# leistung_e7.net
KiCad netlist of a schematic drawn in EAGLE
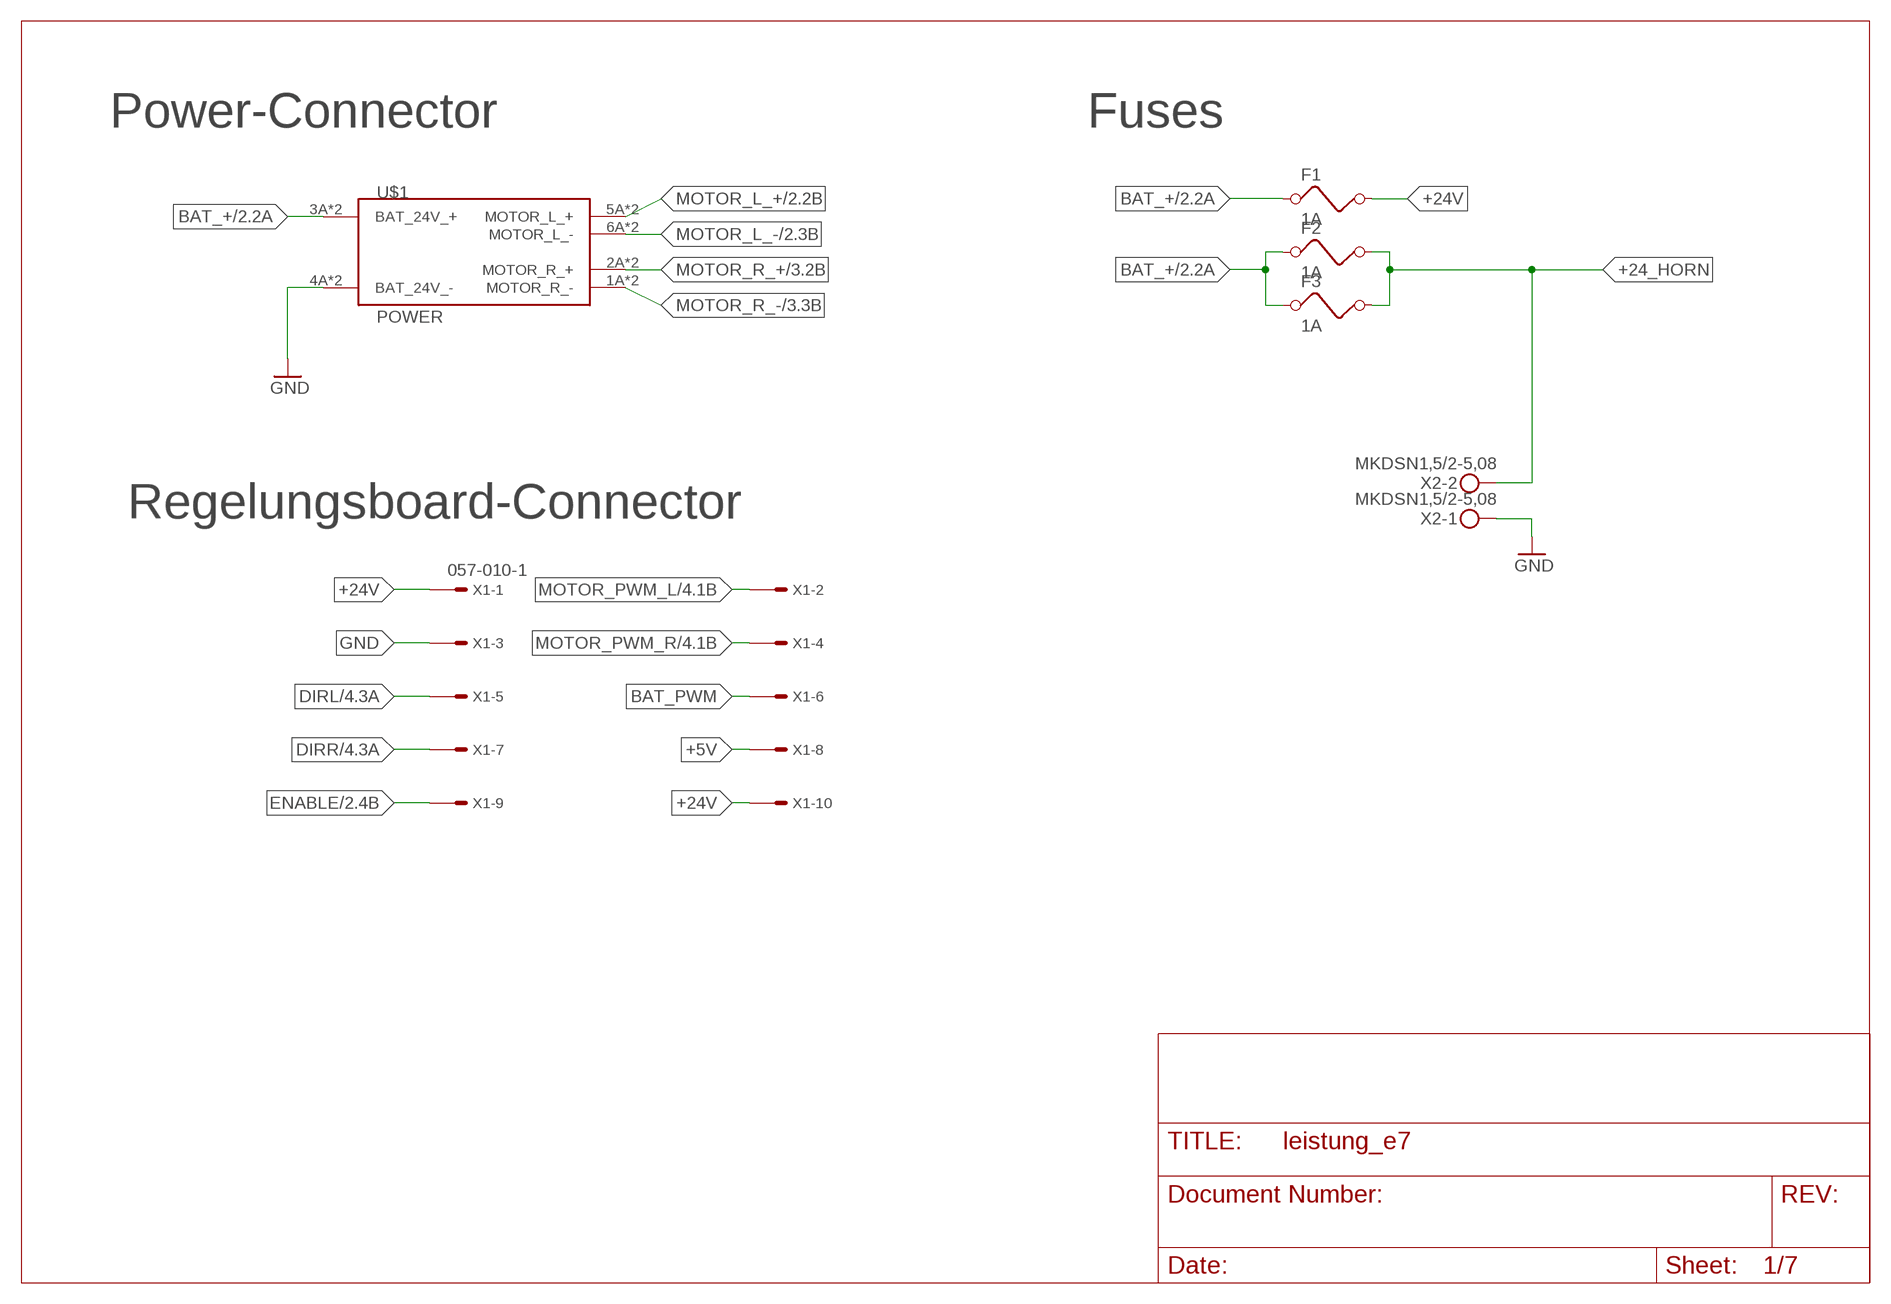
[diagram p0: schematic, sheet 1]
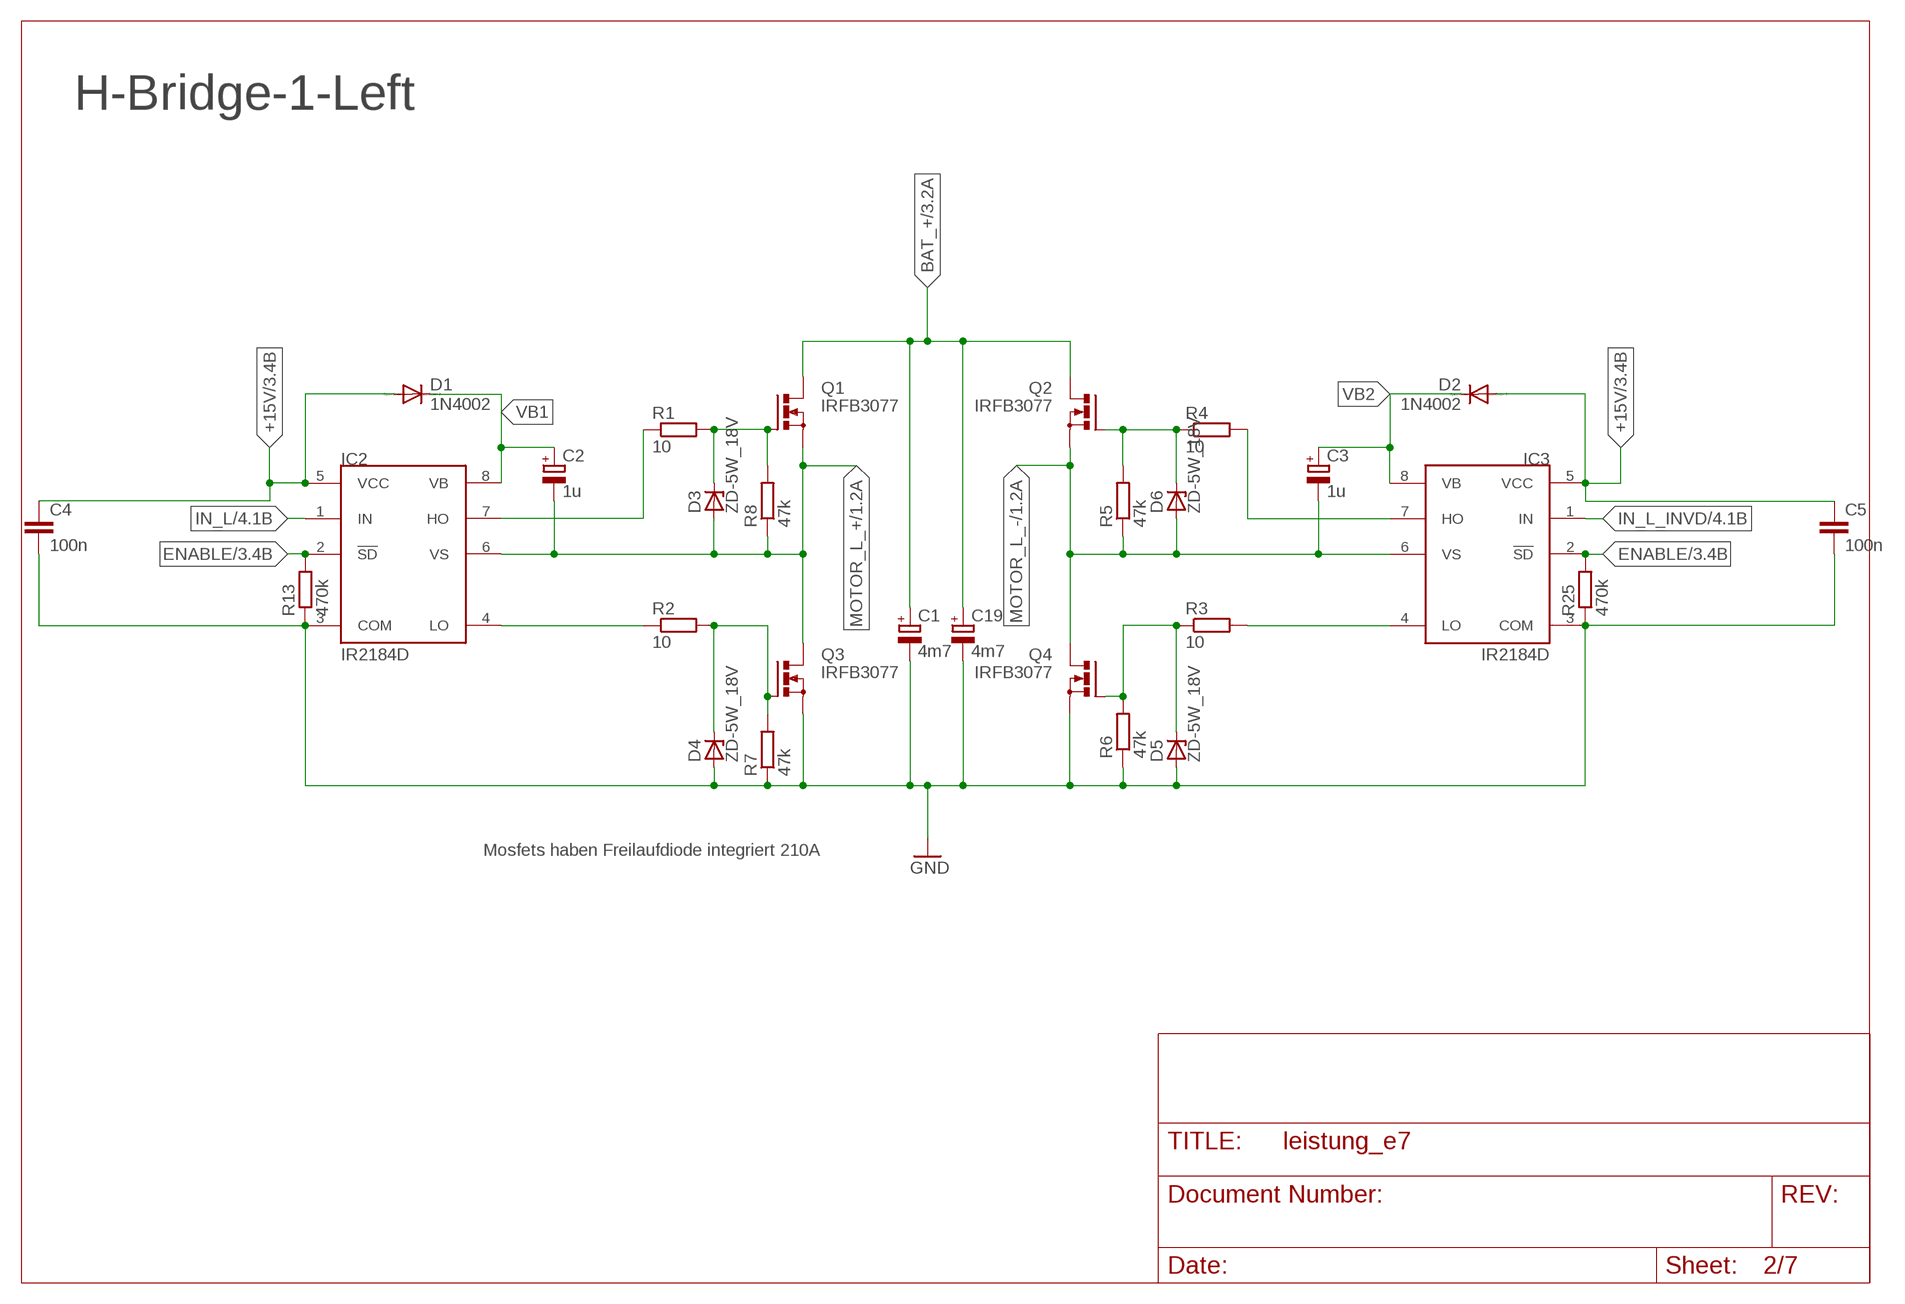
[diagram p1: schematic, sheet 2]
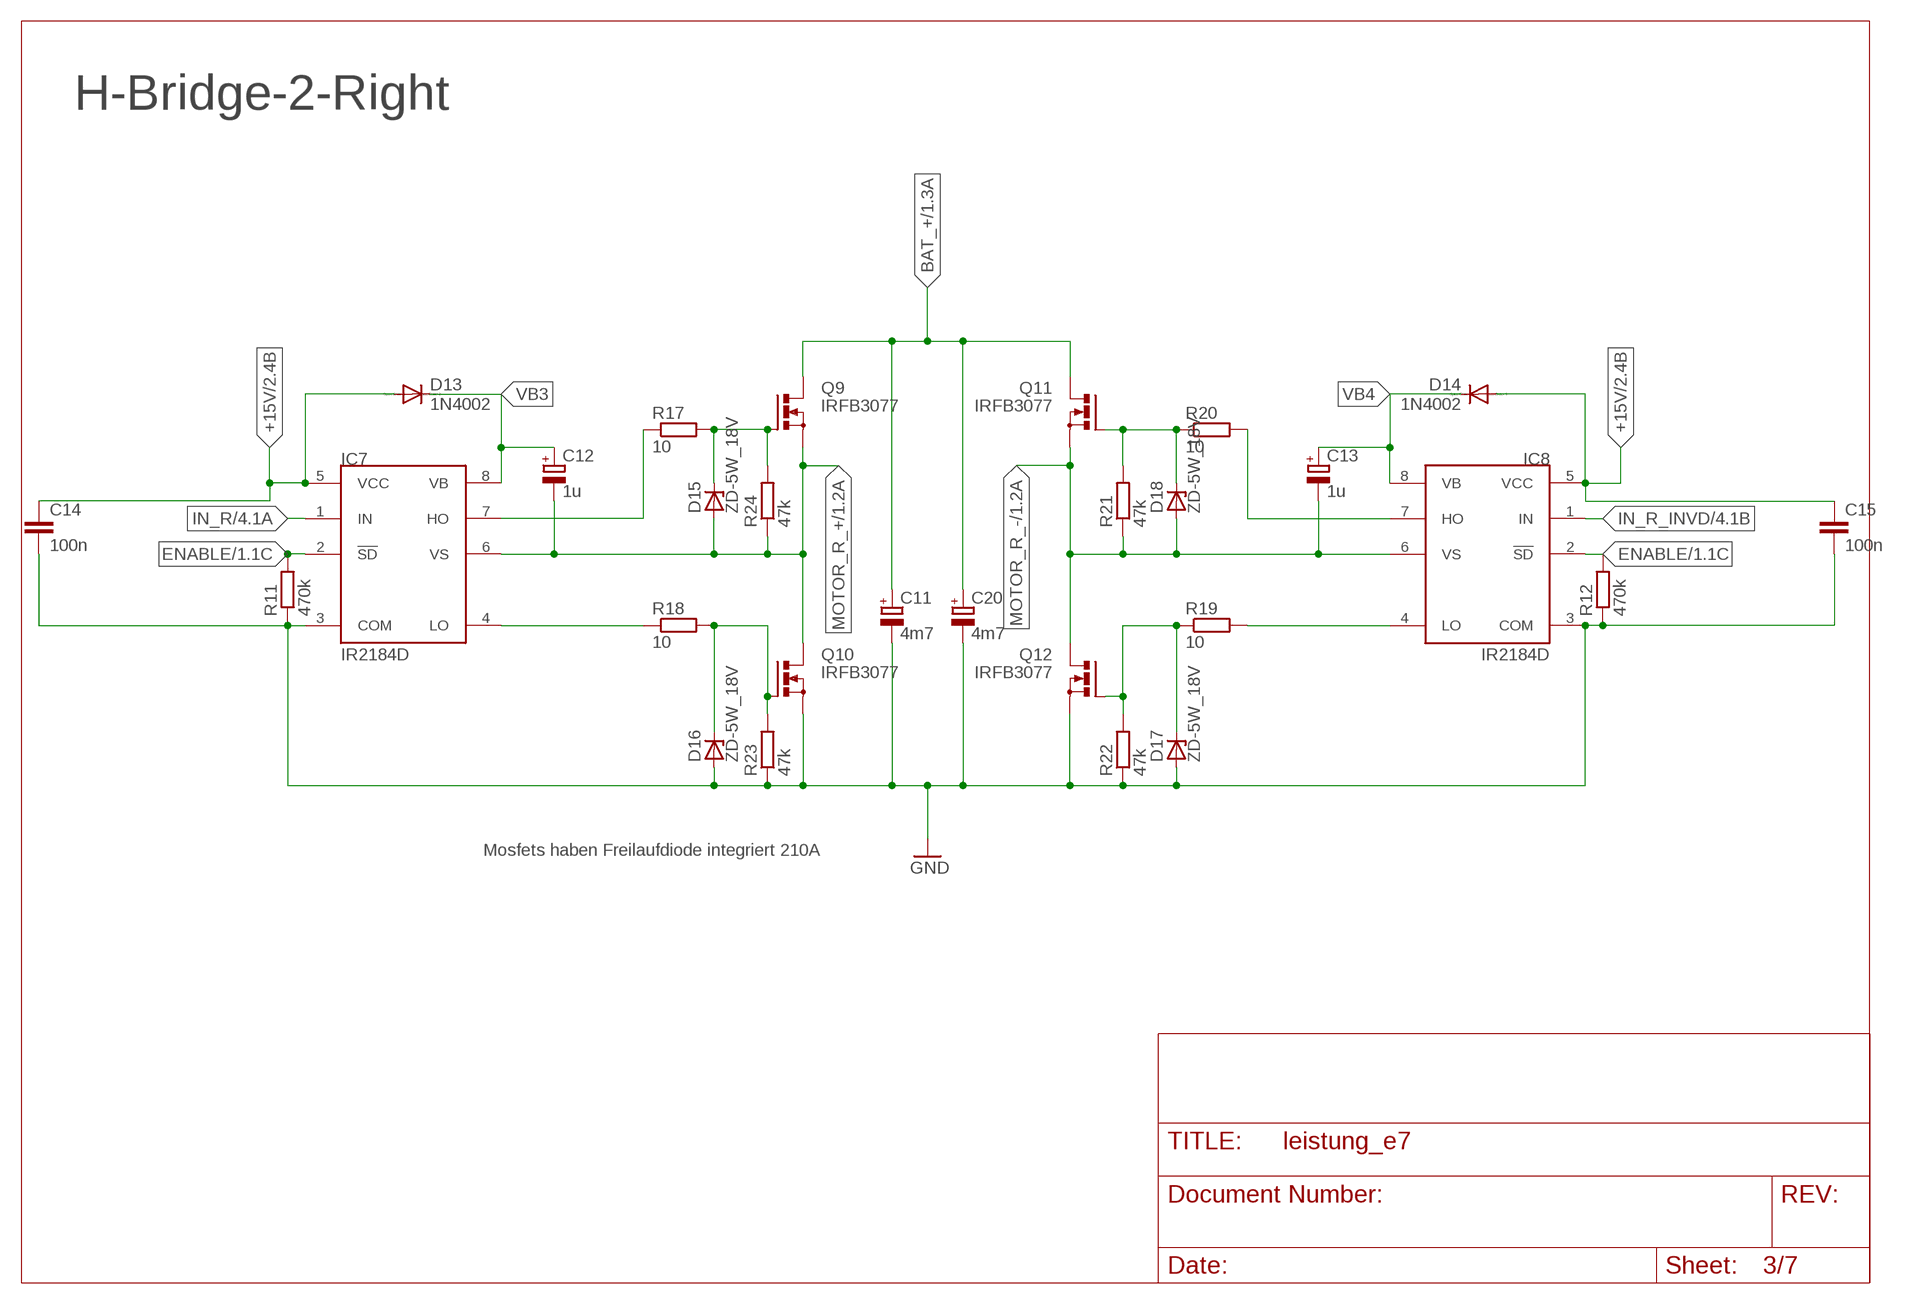
[diagram p2: schematic, sheet 3]
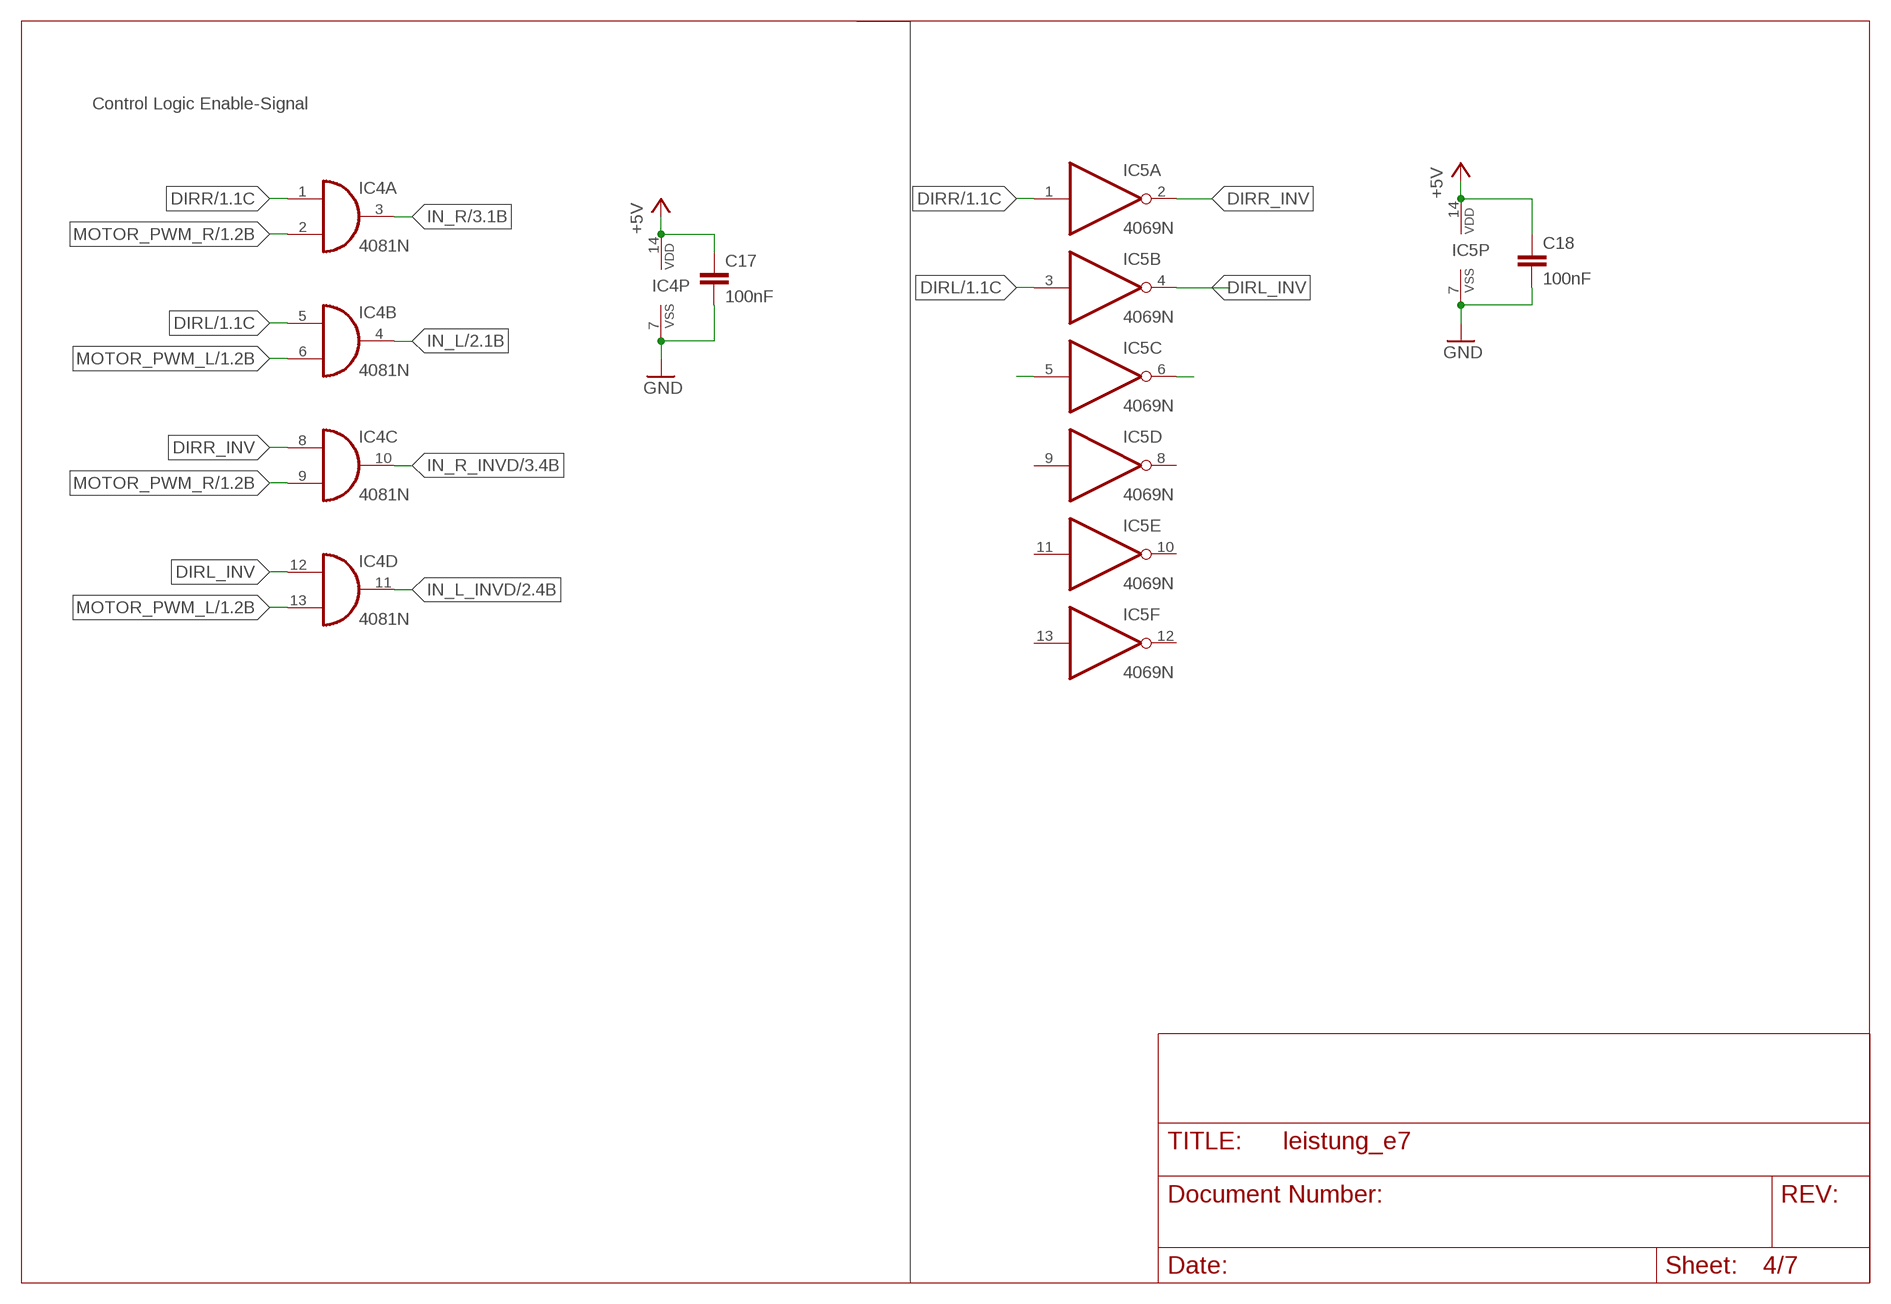
[diagram p3: schematic, sheet 4]
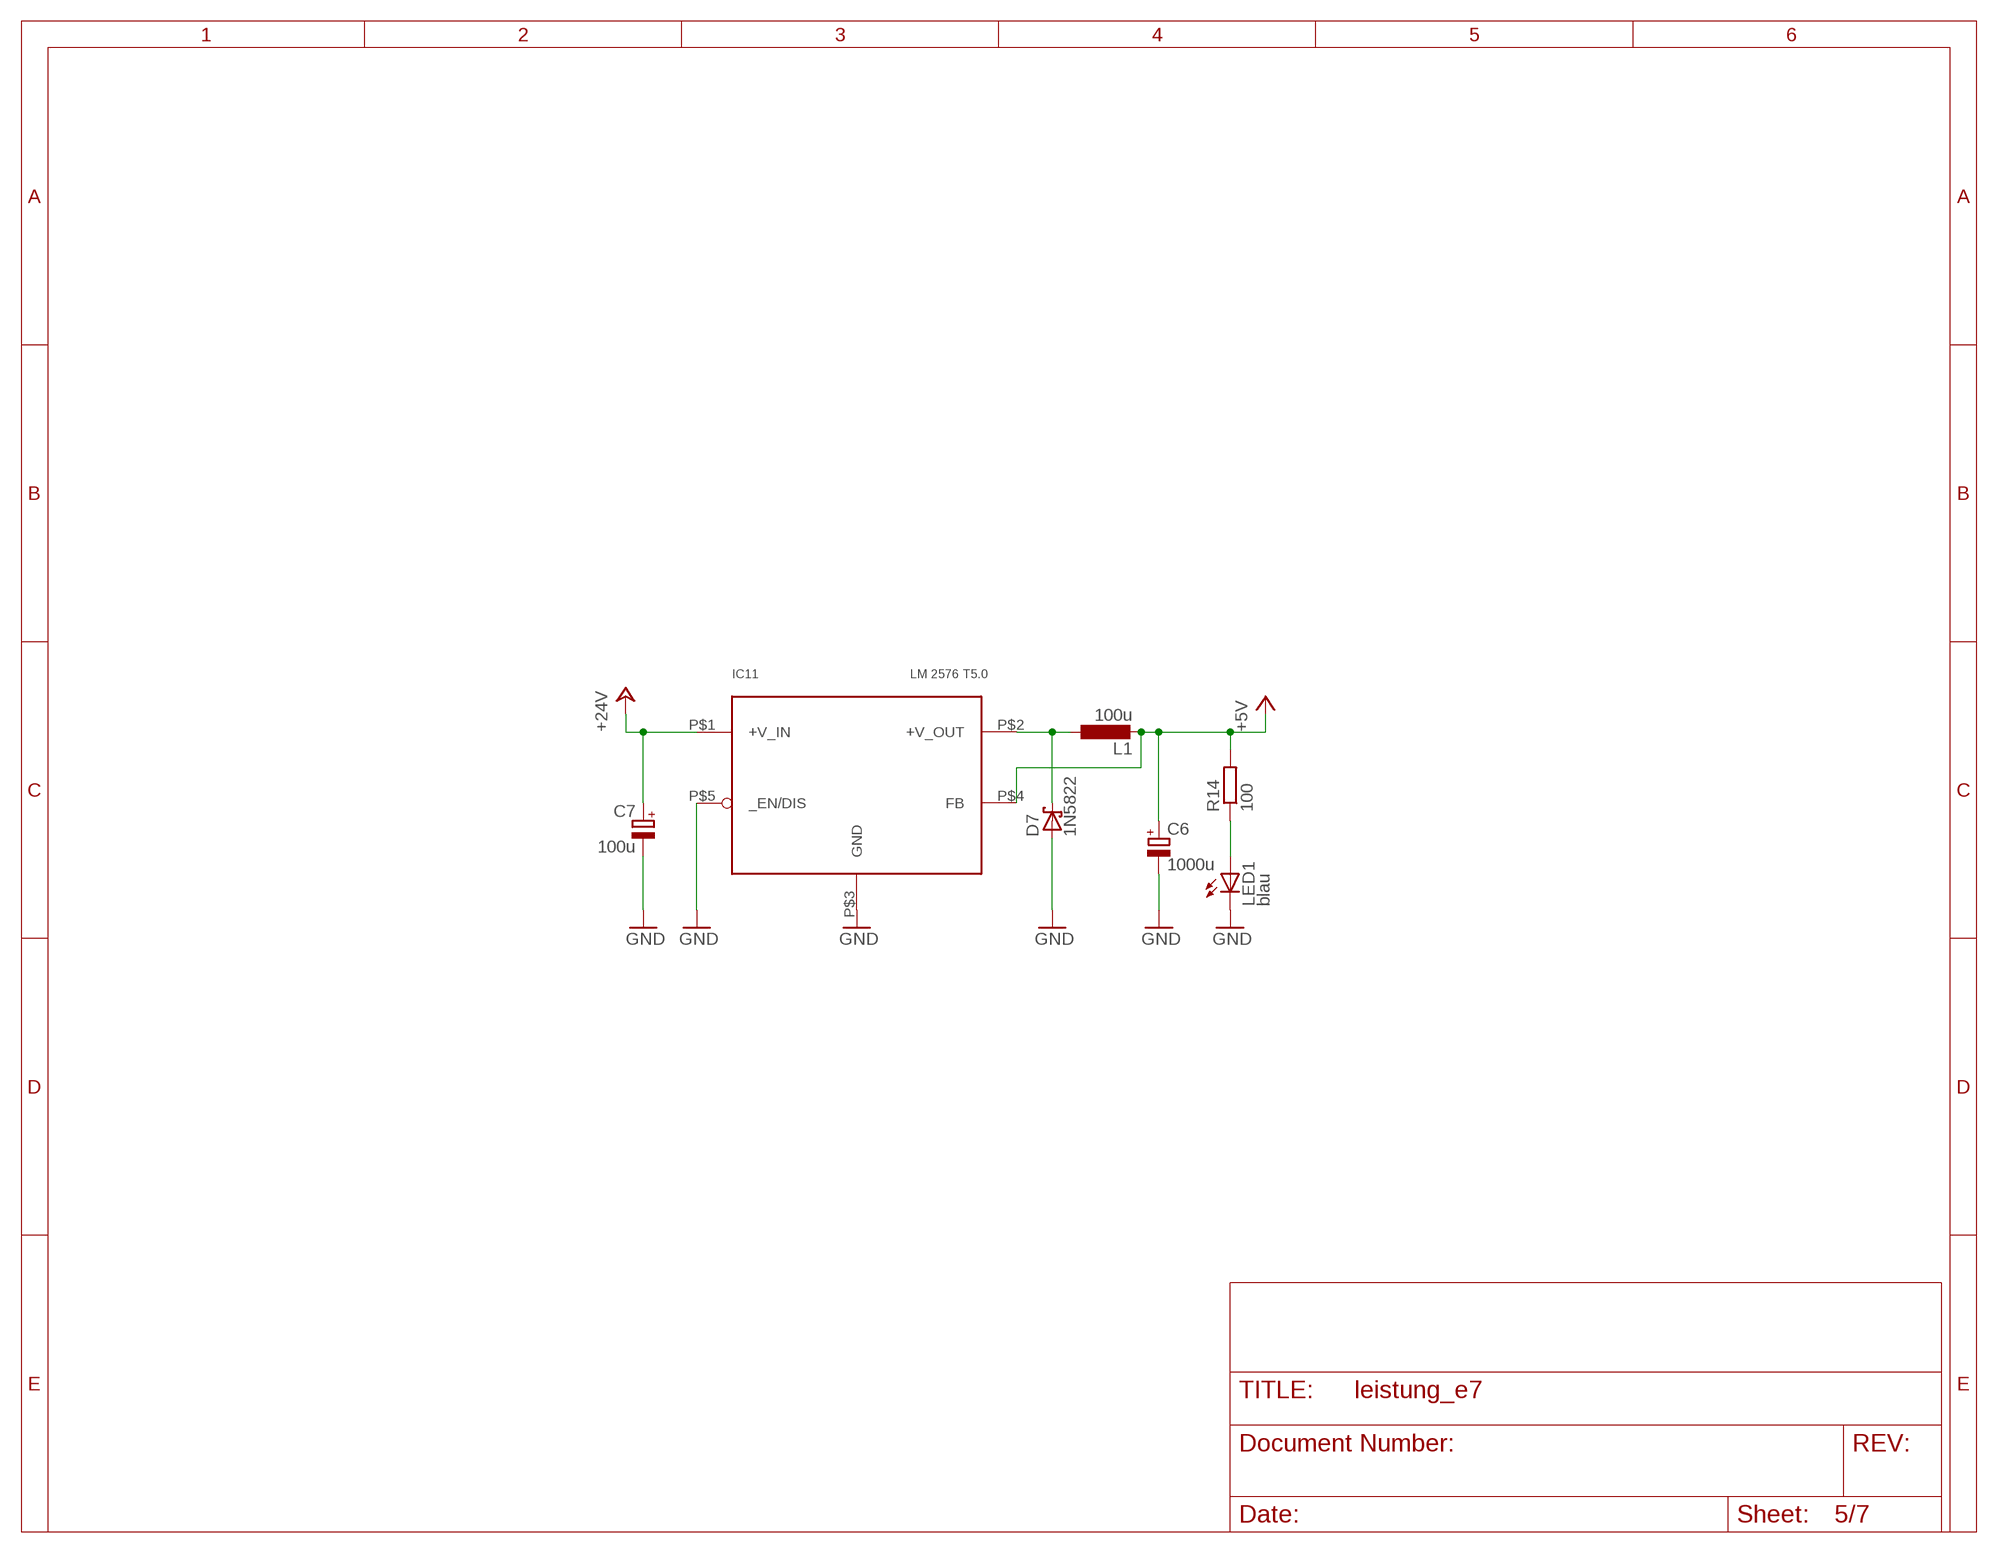
[diagram p4: schematic, sheet 5]
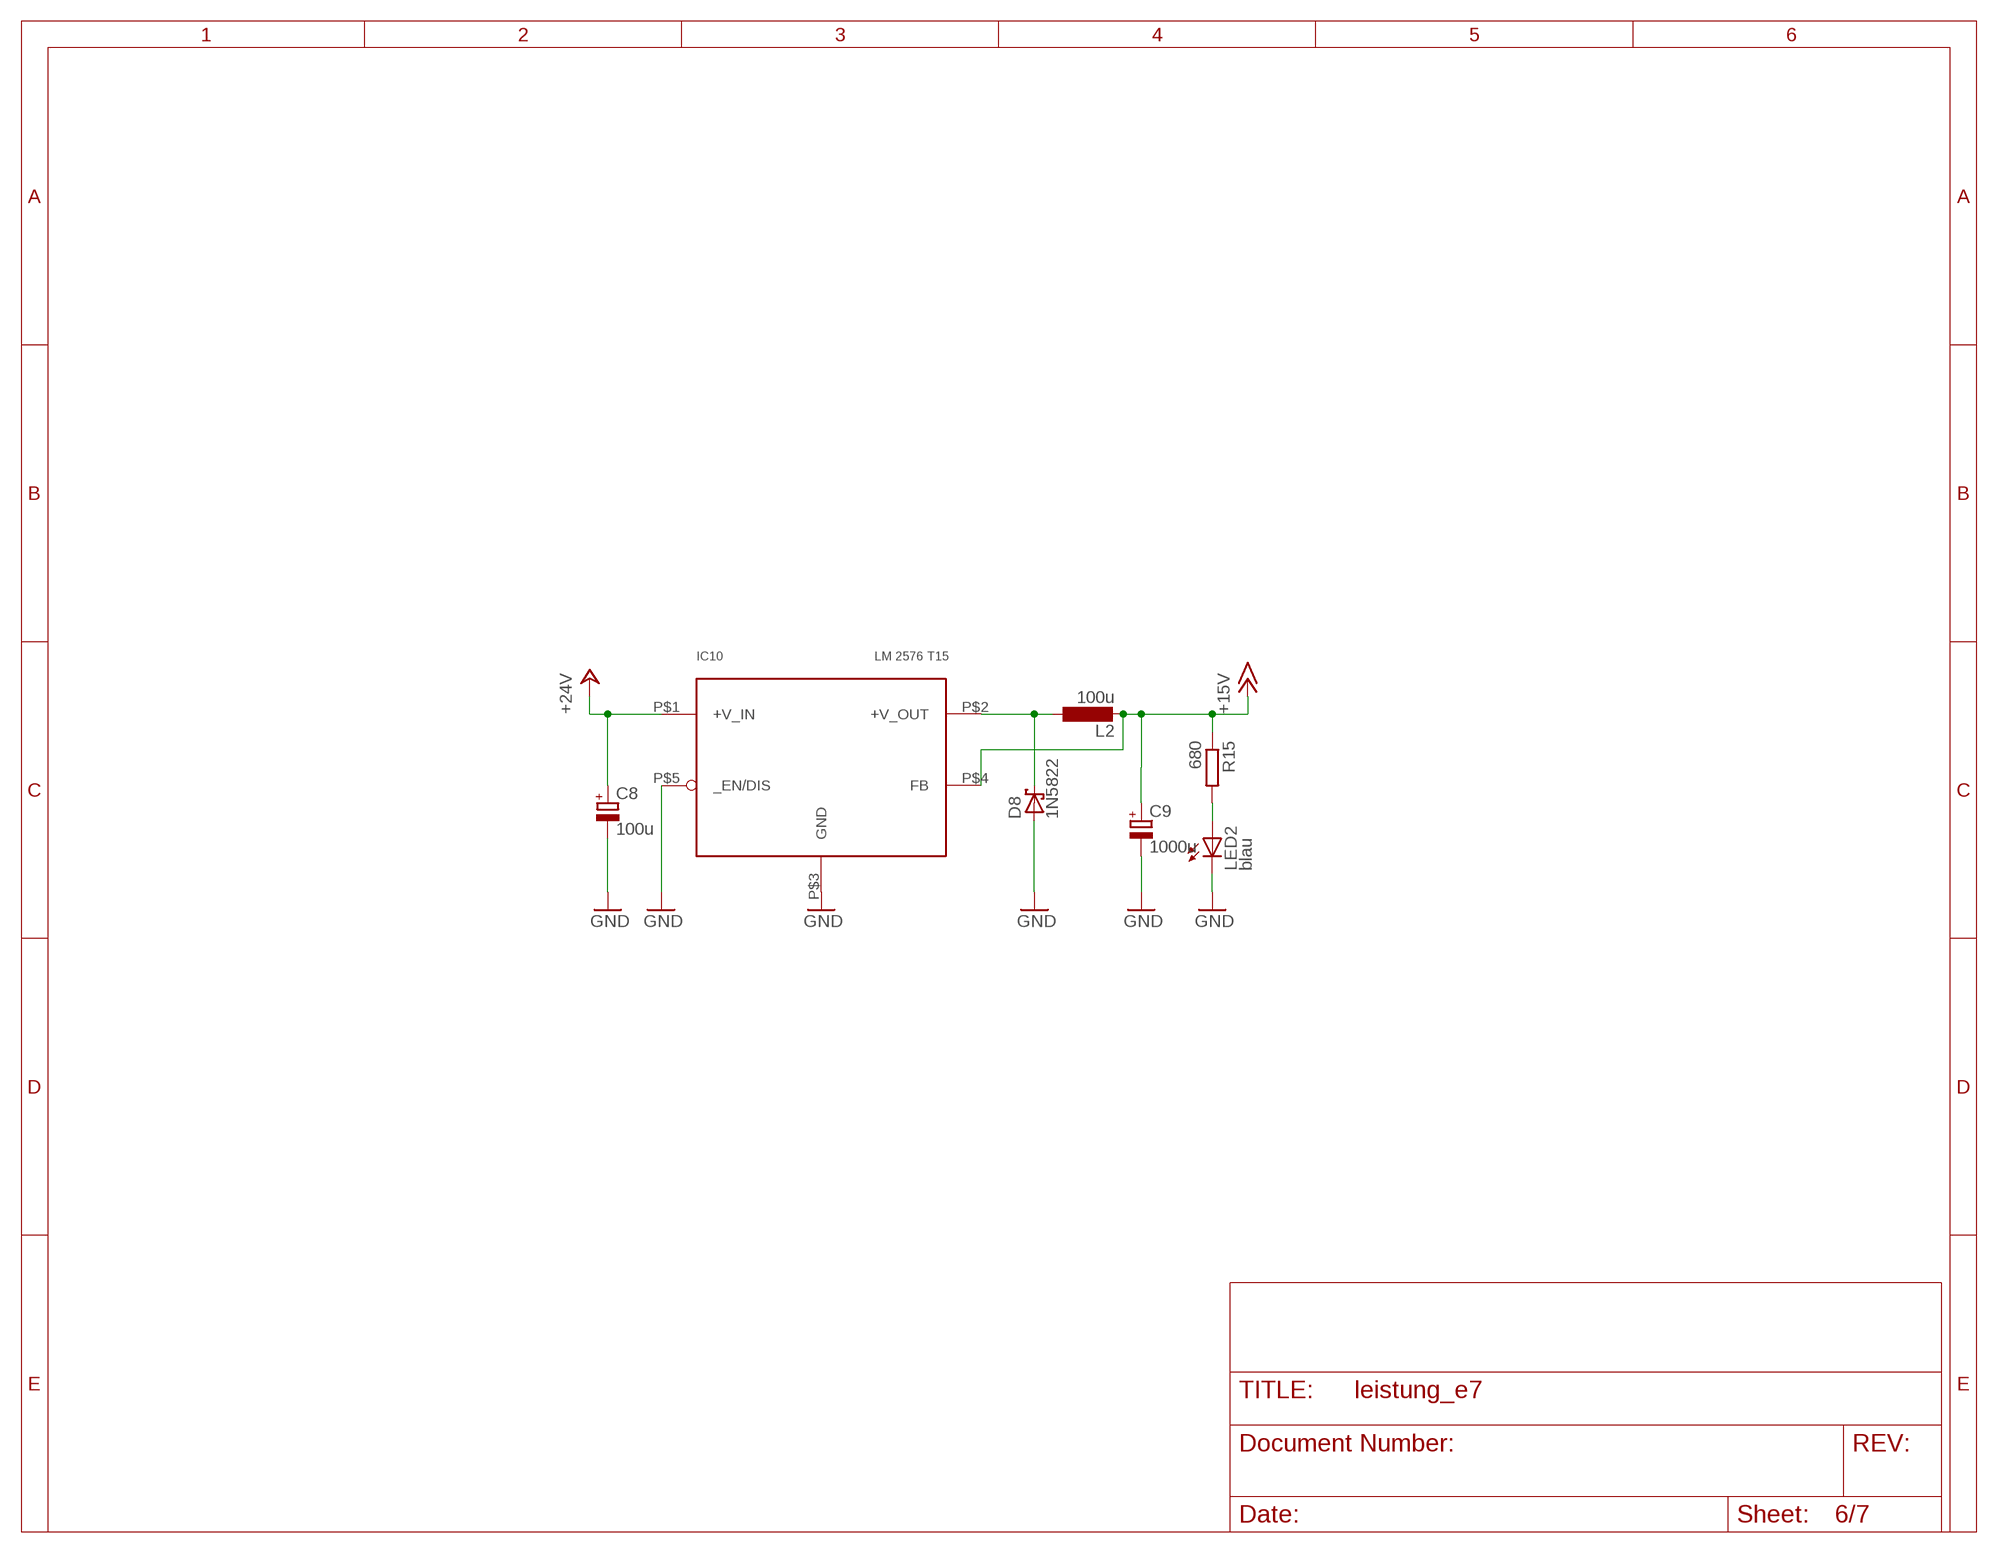
[diagram p5: schematic, sheet 6]
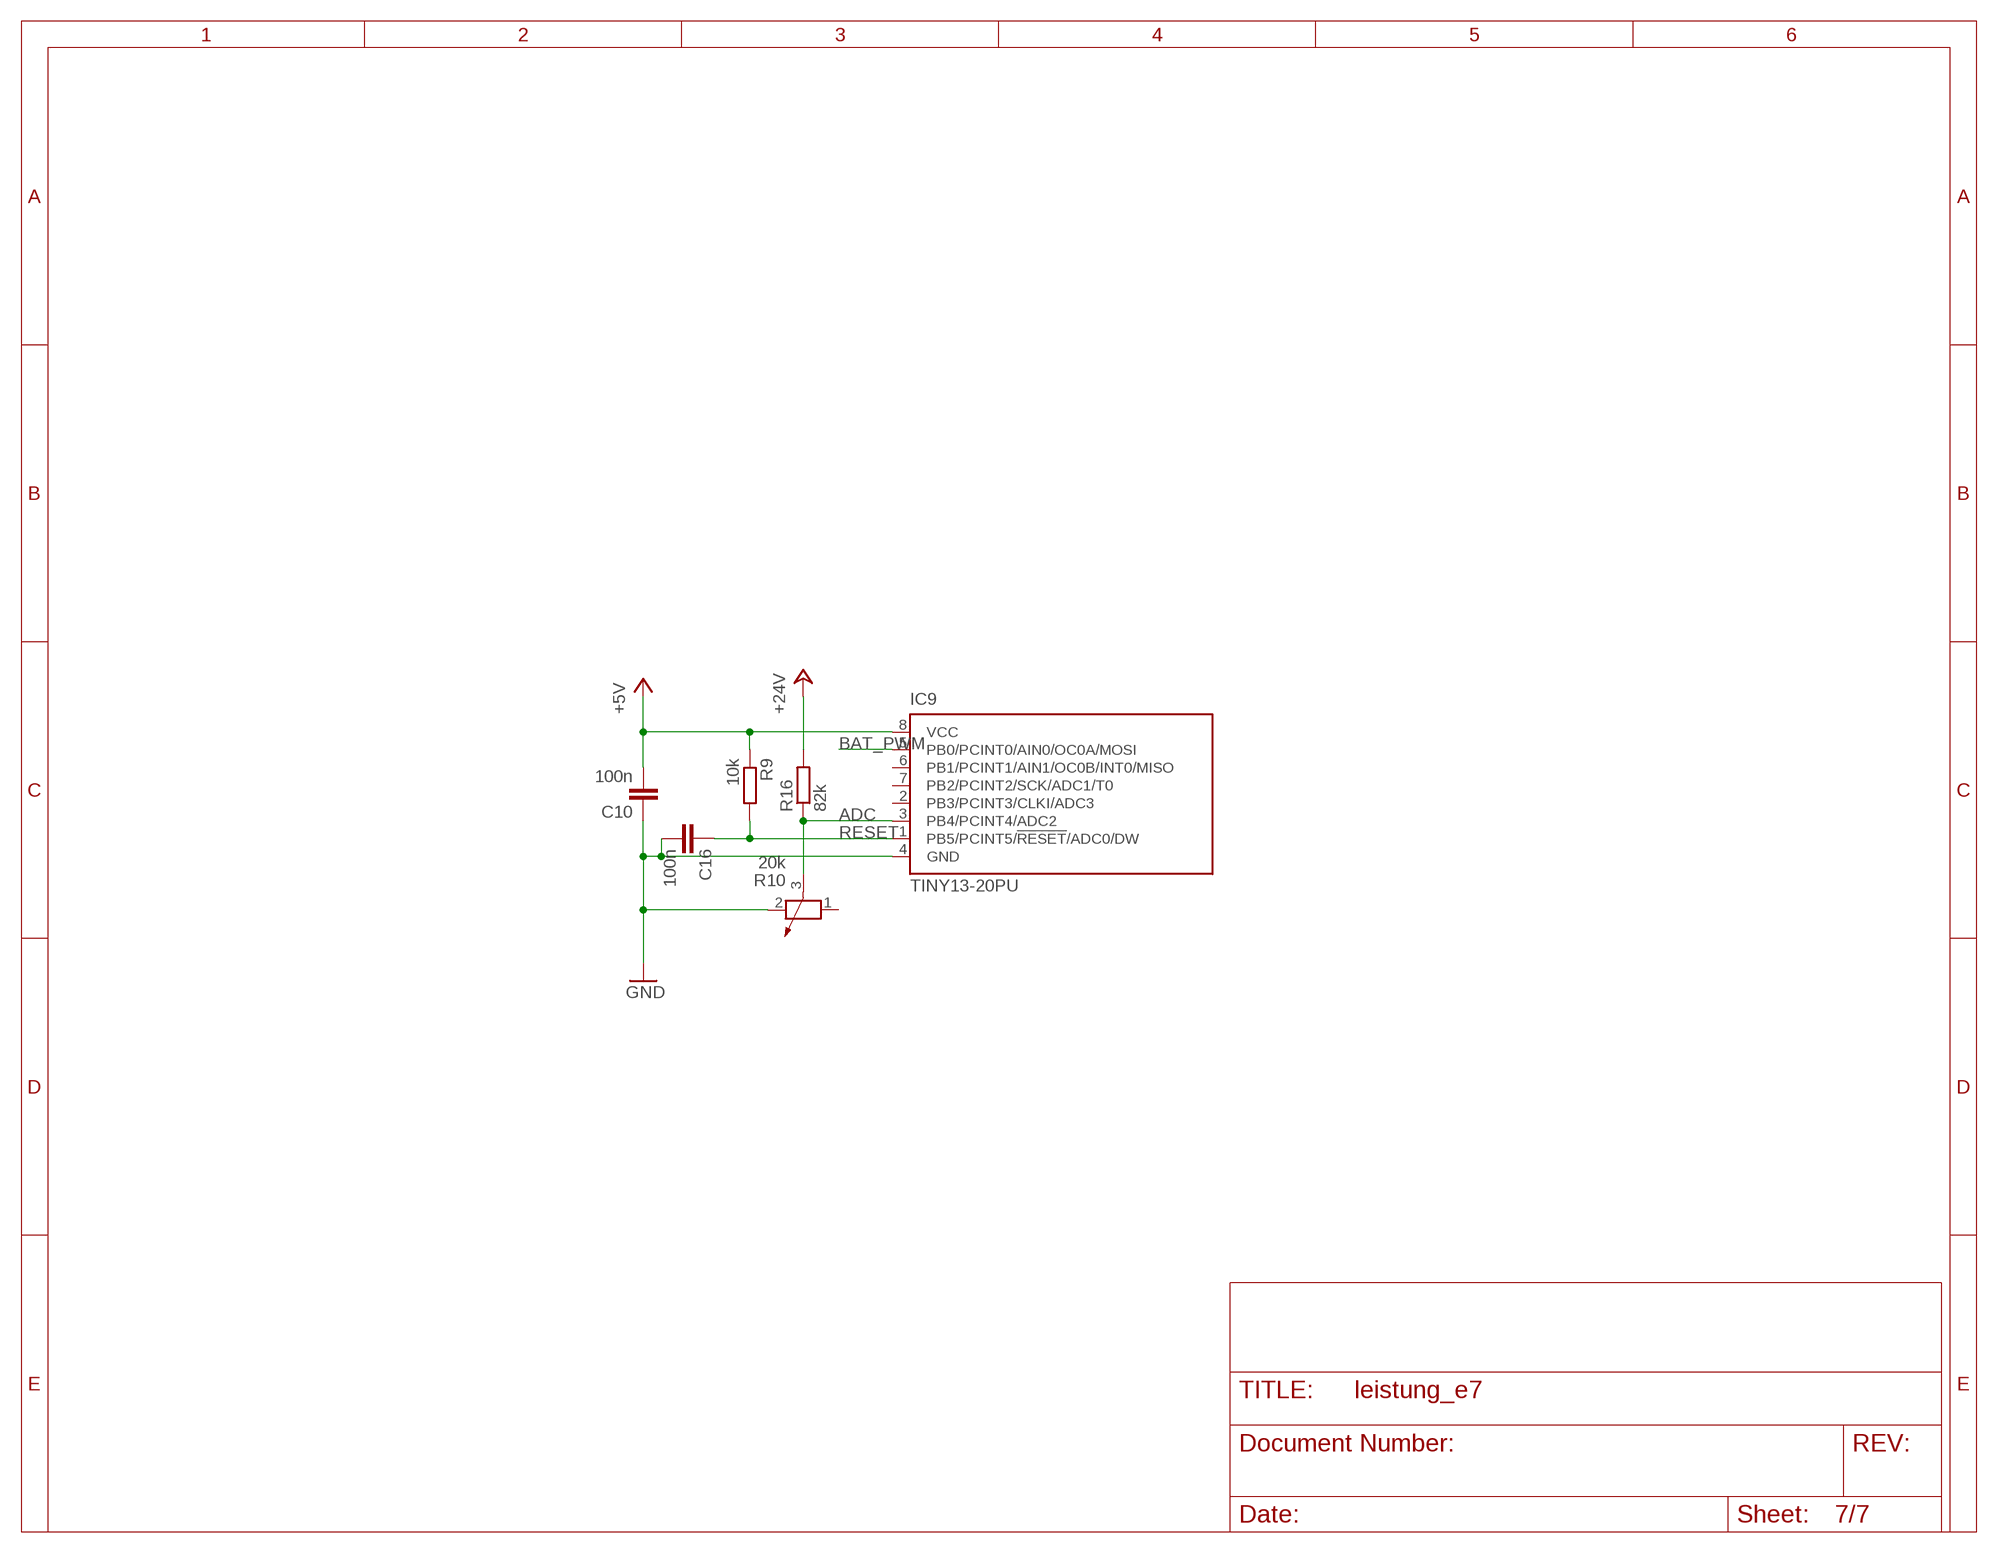
[diagram p6: schematic, sheet 7]

(export (version "E")
  (design (tool "Eeschema 10.0.6"))
  (components
    (comp (ref "C11")
      (value "4m7")
      (footprint "eagle-import:E7,5-18")
      (libsource (lib "eagle-import") (part "CPOL-EUE7.5-18"))
    )
    (comp (ref "C12")
      (value "1u")
      (footprint "eagle-import:E2,5-5")
      (libsource (lib "eagle-import") (part "CPOL-EUE2.5-5"))
    )
    (comp (ref "C13")
      (value "1u")
      (footprint "eagle-import:E2,5-5")
      (libsource (lib "eagle-import") (part "CPOL-EUE2.5-5"))
    )
    (comp (ref "C14")
      (value "100n")
      (footprint "eagle-import:C025-025X050")
      (libsource (lib "eagle-import") (part "C-EU025-025X050"))
    )
    (comp (ref "C15")
      (value "100n")
      (footprint "eagle-import:C025-025X050")
      (libsource (lib "eagle-import") (part "C-EU025-025X050"))
    )
    (comp (ref "C20")
      (value "4m7")
      (footprint "eagle-import:E7,5-18")
      (libsource (lib "eagle-import") (part "CPOL-EUE7.5-18"))
    )
    (comp (ref "D13")
      (value "1N4002")
      (footprint "eagle-import:DO41-10")
      (libsource (lib "eagle-import") (part "1N4004"))
    )
    (comp (ref "D14")
      (value "1N4002")
      (footprint "eagle-import:DO41-10")
      (libsource (lib "eagle-import") (part "1N4004"))
    )
    (comp (ref "D15")
      (value "ZD-5W_18V")
      (footprint "eagle-import:ZDIO-10")
      (libsource (lib "eagle-import") (part "ZENER-DIODEZD-10"))
    )
    (comp (ref "D16")
      (value "ZD-5W_18V")
      (footprint "eagle-import:ZDIO-10")
      (libsource (lib "eagle-import") (part "ZENER-DIODEZD-10"))
    )
    (comp (ref "D17")
      (value "ZD-5W_18V")
      (footprint "eagle-import:ZDIO-10")
      (libsource (lib "eagle-import") (part "ZENER-DIODEZD-10"))
    )
    (comp (ref "D18")
      (value "ZD-5W_18V")
      (footprint "eagle-import:ZDIO-10")
      (libsource (lib "eagle-import") (part "ZENER-DIODEZD-10"))
    )
    (comp (ref "IC7")
      (value "IR2184D")
      (footprint "eagle-import:DIL08")
      (libsource (lib "eagle-import") (part "IR2184D"))
    )
    (comp (ref "IC8")
      (value "IR2184D")
      (footprint "eagle-import:DIL08")
      (libsource (lib "eagle-import") (part "IR2184D"))
    )
    (comp (ref "Q9")
      (value "IRFB3077")
      (footprint "eagle-import:TO220BV")
      (libsource (lib "eagle-import") (part "PMOSFET_NTO220BV"))
    )
    (comp (ref "Q10")
      (value "IRFB3077")
      (footprint "eagle-import:TO220BV")
      (libsource (lib "eagle-import") (part "PMOSFET_NTO220BV"))
    )
    (comp (ref "Q11")
      (value "IRFB3077")
      (footprint "eagle-import:TO220BV")
      (libsource (lib "eagle-import") (part "PMOSFET_NTO220BV"))
    )
    (comp (ref "Q12")
      (value "IRFB3077")
      (footprint "eagle-import:TO220BV")
      (libsource (lib "eagle-import") (part "PMOSFET_NTO220BV"))
    )
    (comp (ref "R11")
      (value "470k")
      (footprint "eagle-import:0207_7")
      (libsource (lib "eagle-import") (part "R-EU_0207/7"))
    )
    (comp (ref "R12")
      (value "470k")
      (footprint "eagle-import:0207_7")
      (libsource (lib "eagle-import") (part "R-EU_0207/7"))
    )
    (comp (ref "R17")
      (value "10")
      (footprint "eagle-import:0207_7")
      (libsource (lib "eagle-import") (part "R-EU_0207/7"))
    )
    (comp (ref "R18")
      (value "10")
      (footprint "eagle-import:0207_7")
      (libsource (lib "eagle-import") (part "R-EU_0207/7"))
    )
    (comp (ref "R19")
      (value "10")
      (footprint "eagle-import:0207_7")
      (libsource (lib "eagle-import") (part "R-EU_0207/7"))
    )
    (comp (ref "R20")
      (value "10")
      (footprint "eagle-import:0207_7")
      (libsource (lib "eagle-import") (part "R-EU_0207/7"))
    )
    (comp (ref "R21")
      (value "47k")
      (footprint "eagle-import:0207_7")
      (libsource (lib "eagle-import") (part "R-EU_0207/7"))
    )
    (comp (ref "R22")
      (value "47k")
      (footprint "eagle-import:0207_7")
      (libsource (lib "eagle-import") (part "R-EU_0207/7"))
    )
    (comp (ref "R23")
      (value "47k")
      (footprint "eagle-import:0207_7")
      (libsource (lib "eagle-import") (part "R-EU_0207/7"))
    )
    (comp (ref "R24")
      (value "47k")
      (footprint "eagle-import:0207_7")
      (libsource (lib "eagle-import") (part "R-EU_0207/7"))
    )
    (comp (ref "C6")
      (value "1000u")
      (footprint "eagle-import:E5-13")
      (libsource (lib "eagle-import") (part "CPOL-EUE5-13"))
    )
    (comp (ref "C7")
      (value "100u")
      (footprint "eagle-import:E2,5-4R")
      (libsource (lib "eagle-import") (part "rcl@1_CPOL-EUE2.5-5V"))
    )
    (comp (ref "D7")
      (value "1N5822")
      (footprint "eagle-import:CB417-15")
      (libsource (lib "eagle-import") (part "SCHOTTKY-DIODECB417-15"))
    )
    (comp (ref "IC11")
      (value "LM 2576 T5.0")
      (footprint "eagle-import:TO220-5_STAGGERED")
      (libsource (lib "eagle-import") (part "LM2576-T05D"))
    )
    (comp (ref "L1")
      (value "100u")
      (footprint "eagle-import:0207_10")
      (libsource (lib "eagle-import") (part "L-EU0207/10"))
    )
    (comp (ref "LED1")
      (value "blau")
      (footprint "eagle-import:LED3MM")
      (libsource (lib "eagle-import") (part "LED3MM"))
    )
    (comp (ref "R14")
      (value "100")
      (footprint "eagle-import:0207_10")
      (libsource (lib "eagle-import") (part "rcl@1_R-EU_0207/10"))
    )
    (comp (ref "C10")
      (value "100n")
      (footprint "eagle-import:C025-025X050")
      (libsource (lib "eagle-import") (part "rcl@1_C-EU025-025X050"))
    )
    (comp (ref "C16")
      (value "100n")
      (footprint "eagle-import:C025-025X050")
      (libsource (lib "eagle-import") (part "rcl@1_C-EU025-025X050"))
    )
    (comp (ref "IC9")
      (value "TINY13-20PU")
      (footprint "eagle-import:DIL08")
      (fields (field (name "MPN") "ATTINY13-20PU"))
      (libsource (lib "eagle-import") (part "TINY13PU-20"))
    )
    (comp (ref "R9")
      (value "10k")
      (footprint "eagle-import:0207_10")
      (libsource (lib "eagle-import") (part "rcl@1_R-EU_0207/10"))
    )
    (comp (ref "R10")
      (value "20k")
      (footprint "eagle-import:PT-10")
      (libsource (lib "eagle-import") (part "POTENTIOMETER_PT-10"))
    )
    (comp (ref "R16")
      (value "82k")
      (footprint "eagle-import:0207_10")
      (libsource (lib "eagle-import") (part "rcl@1_R-EU_0207/10"))
    )
    (comp (ref "F1")
      (value "1A")
      (footprint "eagle-import:FUSE")
      (libsource (lib "eagle-import") (part "FUSE"))
    )
    (comp (ref "F2")
      (value "1A")
      (footprint "eagle-import:FUSE")
      (libsource (lib "eagle-import") (part "FUSE"))
    )
    (comp (ref "F3")
      (value "1A")
      (footprint "eagle-import:FUSE")
      (libsource (lib "eagle-import") (part "FUSE"))
    )
    (comp (ref "U$1")
      (value "POWER")
      (footprint "eagle-import:CON_POWER")
      (libsource (lib "eagle-import") (part "POWER"))
    )
    (comp (ref "X1")
      (value "057-010-1")
      (footprint "eagle-import:057-010-1")
      (libsource (lib "eagle-import") (part "057-010-1"))
    )
    (comp (ref "X2")
      (value "MKDSN1,5/2-5,08")
      (footprint "eagle-import:MKDSN1,5_2-5,08")
      (libsource (lib "eagle-import") (part "MKDSN1,5/2-5,08"))
    )
    (comp (ref "C17")
      (value "100nF")
      (footprint "eagle-import:C025-025X050")
      (libsource (lib "eagle-import") (part "C-EU025-025X050"))
    )
    (comp (ref "C18")
      (value "100nF")
      (footprint "eagle-import:C025-025X050")
      (libsource (lib "eagle-import") (part "C-EU025-025X050"))
    )
    (comp (ref "IC4")
      (value "4081N")
      (footprint "eagle-import:DIL14")
      (libsource (lib "eagle-import") (part "4081N"))
    )
    (comp (ref "IC5")
      (value "4069N")
      (footprint "eagle-import:DIL14")
      (libsource (lib "eagle-import") (part "4069N"))
    )
    (comp (ref "C1")
      (value "4m7")
      (footprint "eagle-import:E7,5-18")
      (libsource (lib "eagle-import") (part "CPOL-EUE7.5-18"))
    )
    (comp (ref "C2")
      (value "1u")
      (footprint "eagle-import:E2,5-5")
      (libsource (lib "eagle-import") (part "CPOL-EUE2.5-5"))
    )
    (comp (ref "C3")
      (value "1u")
      (footprint "eagle-import:E2,5-5")
      (libsource (lib "eagle-import") (part "CPOL-EUE2.5-5"))
    )
    (comp (ref "C4")
      (value "100n")
      (footprint "eagle-import:C025-025X050")
      (libsource (lib "eagle-import") (part "C-EU025-025X050"))
    )
    (comp (ref "C5")
      (value "100n")
      (footprint "eagle-import:C025-025X050")
      (libsource (lib "eagle-import") (part "C-EU025-025X050"))
    )
    (comp (ref "C19")
      (value "4m7")
      (footprint "eagle-import:E7,5-18")
      (libsource (lib "eagle-import") (part "CPOL-EUE7.5-18"))
    )
    (comp (ref "D1")
      (value "1N4002")
      (footprint "eagle-import:DO41-10")
      (libsource (lib "eagle-import") (part "1N4004"))
    )
    (comp (ref "D2")
      (value "1N4002")
      (footprint "eagle-import:DO41-10")
      (libsource (lib "eagle-import") (part "1N4004"))
    )
    (comp (ref "D3")
      (value "ZD-5W_18V")
      (footprint "eagle-import:ZDIO-10")
      (libsource (lib "eagle-import") (part "ZENER-DIODEZD-10"))
    )
    (comp (ref "D4")
      (value "ZD-5W_18V")
      (footprint "eagle-import:ZDIO-10")
      (libsource (lib "eagle-import") (part "ZENER-DIODEZD-10"))
    )
    (comp (ref "D5")
      (value "ZD-5W_18V")
      (footprint "eagle-import:ZDIO-10")
      (libsource (lib "eagle-import") (part "ZENER-DIODEZD-10"))
    )
    (comp (ref "D6")
      (value "ZD-5W_18V")
      (footprint "eagle-import:ZDIO-10")
      (libsource (lib "eagle-import") (part "ZENER-DIODEZD-10"))
    )
    (comp (ref "IC2")
      (value "IR2184D")
      (footprint "eagle-import:DIL08")
      (libsource (lib "eagle-import") (part "IR2184D"))
    )
    (comp (ref "IC3")
      (value "IR2184D")
      (footprint "eagle-import:DIL08")
      (libsource (lib "eagle-import") (part "IR2184D"))
    )
    (comp (ref "Q1")
      (value "IRFB3077")
      (footprint "eagle-import:TO220BV")
      (libsource (lib "eagle-import") (part "PMOSFET_NTO220BV"))
    )
    (comp (ref "Q2")
      (value "IRFB3077")
      (footprint "eagle-import:TO220BV")
      (libsource (lib "eagle-import") (part "PMOSFET_NTO220BV"))
    )
    (comp (ref "Q3")
      (value "IRFB3077")
      (footprint "eagle-import:TO220BV")
      (libsource (lib "eagle-import") (part "PMOSFET_NTO220BV"))
    )
    (comp (ref "Q4")
      (value "IRFB3077")
      (footprint "eagle-import:TO220BV")
      (libsource (lib "eagle-import") (part "PMOSFET_NTO220BV"))
    )
    (comp (ref "R1")
      (value "10")
      (footprint "eagle-import:0207_7")
      (libsource (lib "eagle-import") (part "R-EU_0207/7"))
    )
    (comp (ref "R2")
      (value "10")
      (footprint "eagle-import:0207_7")
      (libsource (lib "eagle-import") (part "R-EU_0207/7"))
    )
    (comp (ref "R3")
      (value "10")
      (footprint "eagle-import:0207_7")
      (libsource (lib "eagle-import") (part "R-EU_0207/7"))
    )
    (comp (ref "R4")
      (value "10")
      (footprint "eagle-import:0207_7")
      (libsource (lib "eagle-import") (part "R-EU_0207/7"))
    )
    (comp (ref "R5")
      (value "47k")
      (footprint "eagle-import:0207_7")
      (libsource (lib "eagle-import") (part "R-EU_0207/7"))
    )
    (comp (ref "R6")
      (value "47k")
      (footprint "eagle-import:0207_7")
      (libsource (lib "eagle-import") (part "R-EU_0207/7"))
    )
    (comp (ref "R7")
      (value "47k")
      (footprint "eagle-import:0207_7")
      (libsource (lib "eagle-import") (part "R-EU_0207/7"))
    )
    (comp (ref "R8")
      (value "47k")
      (footprint "eagle-import:0207_7")
      (libsource (lib "eagle-import") (part "R-EU_0207/7"))
    )
    (comp (ref "R13")
      (value "470k")
      (footprint "eagle-import:0207_7")
      (libsource (lib "eagle-import") (part "R-EU_0207/7"))
    )
    (comp (ref "R25")
      (value "470k")
      (footprint "eagle-import:0207_7")
      (libsource (lib "eagle-import") (part "R-EU_0207/7"))
    )
    (comp (ref "C8")
      (value "100u")
      (footprint "eagle-import:E2,5-7")
      (libsource (lib "eagle-import") (part "rcl@1_CPOL-EUE2.5-7"))
    )
    (comp (ref "C9")
      (value "1000u")
      (footprint "eagle-import:E5-13")
      (libsource (lib "eagle-import") (part "CPOL-EUE5-13"))
    )
    (comp (ref "D8")
      (value "1N5822")
      (footprint "eagle-import:CB429-15")
      (libsource (lib "eagle-import") (part "SCHOTTKY-DIODECB429-15"))
    )
    (comp (ref "IC10")
      (value "LM 2576 T15")
      (footprint "eagle-import:TO220-5_STAGGERED")
      (libsource (lib "eagle-import") (part "LM2576-T05D"))
    )
    (comp (ref "L2")
      (value "100u")
      (footprint "eagle-import:0207_10")
      (libsource (lib "eagle-import") (part "L-EU0207/10"))
    )
    (comp (ref "LED2")
      (value "blau")
      (footprint "eagle-import:LED3MM")
      (libsource (lib "eagle-import") (part "LED3MM"))
    )
    (comp (ref "R15")
      (value "680")
      (footprint "eagle-import:0207_10")
      (libsource (lib "eagle-import") (part "rcl@1_R-EU_0207/10"))
    )
  )
  (nets
    (net (code "1") (name "+5V") (class "Default")
      (node (ref "C10") (pin "2") (pinfunction "2_2") (pintype "passive"))
      (node (ref "C17") (pin "1") (pinfunction "1_1") (pintype "passive"))
      (node (ref "C18") (pin "1") (pinfunction "1_1") (pintype "passive"))
      (node (ref "C6") (pin "+") (pinfunction "+_+") (pintype "passive"))
      (node (ref "IC11") (pin "P$4") (pinfunction "FB_P$4") (pintype "input"))
      (node (ref "IC4") (pin "14") (pinfunction "VDD_14") (pintype "power_in"))
      (node (ref "IC5") (pin "14") (pinfunction "VDD_14") (pintype "power_in"))
      (node (ref "IC9") (pin "8") (pinfunction "VCC_8") (pintype "power_in"))
      (node (ref "L1") (pin "2") (pinfunction "2_2") (pintype "passive"))
      (node (ref "R14") (pin "2") (pinfunction "2_2") (pintype "passive"))
      (node (ref "R9") (pin "1") (pinfunction "1_1") (pintype "passive"))
      (node (ref "X1") (pin "8") (pinfunction "S_8") (pintype "passive"))
    )
    (net (code "2") (name "+15V") (class "Default")
      (node (ref "C14") (pin "1") (pinfunction "1_1") (pintype "passive"))
      (node (ref "C15") (pin "1") (pinfunction "1_1") (pintype "passive"))
      (node (ref "C4") (pin "1") (pinfunction "1_1") (pintype "passive"))
      (node (ref "C5") (pin "1") (pinfunction "1_1") (pintype "passive"))
      (node (ref "C9") (pin "+") (pinfunction "+_+") (pintype "passive"))
      (node (ref "D1") (pin "A") (pinfunction "A_A") (pintype "passive"))
      (node (ref "D13") (pin "A") (pinfunction "A_A") (pintype "passive"))
      (node (ref "D14") (pin "A") (pinfunction "A_A") (pintype "passive"))
      (node (ref "D2") (pin "A") (pinfunction "A_A") (pintype "passive"))
      (node (ref "IC10") (pin "P$4") (pinfunction "FB_P$4") (pintype "input"))
      (node (ref "IC2") (pin "5") (pinfunction "VCC_5") (pintype "power_in"))
      (node (ref "IC3") (pin "5") (pinfunction "VCC_5") (pintype "power_in"))
      (node (ref "IC7") (pin "5") (pinfunction "VCC_5") (pintype "power_in"))
      (node (ref "IC8") (pin "5") (pinfunction "VCC_5") (pintype "power_in"))
      (node (ref "L2") (pin "2") (pinfunction "2_2") (pintype "passive"))
      (node (ref "R15") (pin "1") (pinfunction "1_1") (pintype "passive"))
    )
    (net (code "3") (name "+24V") (class "Default")
      (node (ref "C7") (pin "+") (pinfunction "+_+") (pintype "passive"))
      (node (ref "C8") (pin "+") (pinfunction "+_+") (pintype "passive"))
      (node (ref "F1") (pin "2") (pinfunction "2_2") (pintype "passive"))
      (node (ref "IC10") (pin "P$1") (pinfunction "+V_IN_P$1") (pintype "input"))
      (node (ref "IC11") (pin "P$1") (pinfunction "+V_IN_P$1") (pintype "input"))
      (node (ref "R16") (pin "2") (pinfunction "2_2") (pintype "passive"))
      (node (ref "X1") (pin "1") (pinfunction "S_1") (pintype "passive"))
      (node (ref "X1") (pin "10") (pinfunction "S_10") (pintype "passive"))
    )
    (net (code "4") (name "+24_HORN") (class "Default")
      (node (ref "F2") (pin "2") (pinfunction "2_2") (pintype "passive"))
      (node (ref "F3") (pin "2") (pinfunction "2_2") (pintype "passive"))
      (node (ref "X2") (pin "2") (pinfunction "KL_2") (pintype "passive"))
    )
    (net (code "5") (name "ADC") (class "Default")
      (node (ref "IC9") (pin "3") (pinfunction "PB4/PCINT4/ADC2_3") (pintype "bidirectional"))
      (node (ref "R10") (pin "3") (pinfunction "3_3") (pintype "passive"))
      (node (ref "R16") (pin "1") (pinfunction "1_1") (pintype "passive"))
    )
    (net (code "6") (name "BAT_+") (class "Default")
      (node (ref "C1") (pin "+") (pinfunction "+_+") (pintype "passive"))
      (node (ref "C11") (pin "+") (pinfunction "+_+") (pintype "passive"))
      (node (ref "C19") (pin "+") (pinfunction "+_+") (pintype "passive"))
      (node (ref "C20") (pin "+") (pinfunction "+_+") (pintype "passive"))
      (node (ref "F1") (pin "1") (pinfunction "1_1") (pintype "passive"))
      (node (ref "F2") (pin "1") (pinfunction "1_1") (pintype "passive"))
      (node (ref "F3") (pin "1") (pinfunction "1_1") (pintype "passive"))
      (node (ref "Q1") (pin "D") (pinfunction "D_D") (pintype "passive"))
      (node (ref "Q11") (pin "D") (pinfunction "D_D") (pintype "passive"))
      (node (ref "Q2") (pin "D") (pinfunction "D_D") (pintype "passive"))
      (node (ref "Q9") (pin "D") (pinfunction "D_D") (pintype "passive"))
      (node (ref "U$1") (pin "3A") (pinfunction "BAT_24V_+_3A") (pintype "power_in"))
      (node (ref "U$1") (pin "3B") (pinfunction "BAT_24V_+_3B") (pintype "power_in"))
    )
    (net (code "7") (name "BAT_PWM") (class "Default")
      (node (ref "IC9") (pin "5") (pinfunction "PB0/PCINT0/AIN0/OC0A/MOSI_5") (pintype "bidirectional"))
      (node (ref "X1") (pin "6") (pinfunction "S_6") (pintype "passive"))
    )
    (net (code "8") (name "DIRL") (class "Default")
      (node (ref "IC4") (pin "5") (pinfunction "I0_5") (pintype "input"))
      (node (ref "IC5") (pin "3") (pinfunction "I_3") (pintype "input"))
      (node (ref "X1") (pin "5") (pinfunction "S_5") (pintype "passive"))
    )
    (net (code "9") (name "DIRL_INV") (class "Default")
      (node (ref "IC4") (pin "12") (pinfunction "I0_12") (pintype "input"))
      (node (ref "IC5") (pin "4") (pinfunction "O_4") (pintype "output"))
    )
    (net (code "10") (name "DIRR") (class "Default")
      (node (ref "IC4") (pin "1") (pinfunction "I0_1") (pintype "input"))
      (node (ref "IC5") (pin "1") (pinfunction "I_1") (pintype "input"))
      (node (ref "X1") (pin "7") (pinfunction "S_7") (pintype "passive"))
    )
    (net (code "11") (name "DIRR_INV") (class "Default")
      (node (ref "IC4") (pin "8") (pinfunction "I0_8") (pintype "input"))
      (node (ref "IC5") (pin "2") (pinfunction "O_2") (pintype "output"))
    )
    (net (code "12") (name "ENABLE") (class "Default")
      (node (ref "IC2") (pin "2") (pinfunction "~{SD}_2") (pintype "input"))
      (node (ref "IC3") (pin "2") (pinfunction "~{SD}_2") (pintype "input"))
      (node (ref "IC7") (pin "2") (pinfunction "~{SD}_2") (pintype "input"))
      (node (ref "IC8") (pin "2") (pinfunction "~{SD}_2") (pintype "input"))
      (node (ref "R11") (pin "2") (pinfunction "2_2") (pintype "passive"))
      (node (ref "R12") (pin "2") (pinfunction "2_2") (pintype "passive"))
      (node (ref "R13") (pin "2") (pinfunction "2_2") (pintype "passive"))
      (node (ref "R25") (pin "2") (pinfunction "2_2") (pintype "passive"))
      (node (ref "X1") (pin "9") (pinfunction "S_9") (pintype "passive"))
    )
    (net (code "13") (name "GND") (class "Default")
      (node (ref "C1") (pin "-") (pinfunction "-_-") (pintype "passive"))
      (node (ref "C10") (pin "1") (pinfunction "1_1") (pintype "passive"))
      (node (ref "C11") (pin "-") (pinfunction "-_-") (pintype "passive"))
      (node (ref "C14") (pin "2") (pinfunction "2_2") (pintype "passive"))
      (node (ref "C15") (pin "2") (pinfunction "2_2") (pintype "passive"))
      (node (ref "C16") (pin "2") (pinfunction "2_2") (pintype "passive"))
      (node (ref "C17") (pin "2") (pinfunction "2_2") (pintype "passive"))
      (node (ref "C18") (pin "2") (pinfunction "2_2") (pintype "passive"))
      (node (ref "C19") (pin "-") (pinfunction "-_-") (pintype "passive"))
      (node (ref "C20") (pin "-") (pinfunction "-_-") (pintype "passive"))
      (node (ref "C4") (pin "2") (pinfunction "2_2") (pintype "passive"))
      (node (ref "C5") (pin "2") (pinfunction "2_2") (pintype "passive"))
      (node (ref "C6") (pin "-") (pinfunction "-_-") (pintype "passive"))
      (node (ref "C7") (pin "-") (pinfunction "-_-") (pintype "passive"))
      (node (ref "C8") (pin "-") (pinfunction "-_-") (pintype "passive"))
      (node (ref "C9") (pin "-") (pinfunction "-_-") (pintype "passive"))
      (node (ref "D16") (pin "A") (pinfunction "A_A") (pintype "passive"))
      (node (ref "D17") (pin "A") (pinfunction "A_A") (pintype "passive"))
      (node (ref "D4") (pin "A") (pinfunction "A_A") (pintype "passive"))
      (node (ref "D5") (pin "A") (pinfunction "A_A") (pintype "passive"))
      (node (ref "D7") (pin "A") (pinfunction "A_A") (pintype "passive"))
      (node (ref "D8") (pin "A") (pinfunction "A_A") (pintype "passive"))
      (node (ref "IC10") (pin "P$3") (pinfunction "GND_P$3") (pintype "power_in"))
      (node (ref "IC10") (pin "P$5") (pinfunction "_EN/DIS_P$5") (pintype "input"))
      (node (ref "IC11") (pin "P$3") (pinfunction "GND_P$3") (pintype "power_in"))
      (node (ref "IC11") (pin "P$5") (pinfunction "_EN/DIS_P$5") (pintype "input"))
      (node (ref "IC2") (pin "3") (pinfunction "COM_3") (pintype "power_in"))
      (node (ref "IC3") (pin "3") (pinfunction "COM_3") (pintype "power_in"))
      (node (ref "IC4") (pin "7") (pinfunction "VSS_7") (pintype "power_in"))
      (node (ref "IC5") (pin "7") (pinfunction "VSS_7") (pintype "power_in"))
      (node (ref "IC7") (pin "3") (pinfunction "COM_3") (pintype "power_in"))
      (node (ref "IC8") (pin "3") (pinfunction "COM_3") (pintype "power_in"))
      (node (ref "IC9") (pin "4") (pinfunction "GND_4") (pintype "power_in"))
      (node (ref "LED1") (pin "K") (pinfunction "C_K") (pintype "passive"))
      (node (ref "LED2") (pin "K") (pinfunction "C_K") (pintype "passive"))
      (node (ref "Q10") (pin "S") (pinfunction "S_S") (pintype "passive"))
      (node (ref "Q12") (pin "S") (pinfunction "S_S") (pintype "passive"))
      (node (ref "Q3") (pin "S") (pinfunction "S_S") (pintype "passive"))
      (node (ref "Q4") (pin "S") (pinfunction "S_S") (pintype "passive"))
      (node (ref "R10") (pin "2") (pinfunction "2_2") (pintype "passive"))
      (node (ref "R11") (pin "1") (pinfunction "1_1") (pintype "passive"))
      (node (ref "R12") (pin "1") (pinfunction "1_1") (pintype "passive"))
      (node (ref "R13") (pin "1") (pinfunction "1_1") (pintype "passive"))
      (node (ref "R22") (pin "1") (pinfunction "1_1") (pintype "passive"))
      (node (ref "R23") (pin "1") (pinfunction "1_1") (pintype "passive"))
      (node (ref "R25") (pin "1") (pinfunction "1_1") (pintype "passive"))
      (node (ref "R6") (pin "1") (pinfunction "1_1") (pintype "passive"))
      (node (ref "R7") (pin "1") (pinfunction "1_1") (pintype "passive"))
      (node (ref "U$1") (pin "4A") (pinfunction "BAT_24V_-_4A") (pintype "power_in"))
      (node (ref "U$1") (pin "4B") (pinfunction "BAT_24V_-_4B") (pintype "power_in"))
      (node (ref "X1") (pin "3") (pinfunction "S_3") (pintype "passive"))
      (node (ref "X2") (pin "1") (pinfunction "KL_1") (pintype "passive"))
    )
    (net (code "14") (name "IN_L") (class "Default")
      (node (ref "IC2") (pin "1") (pinfunction "IN_1") (pintype "input"))
      (node (ref "IC4") (pin "4") (pinfunction "O_4") (pintype "output"))
    )
    (net (code "15") (name "IN_L_INVD") (class "Default")
      (node (ref "IC3") (pin "1") (pinfunction "IN_1") (pintype "input"))
      (node (ref "IC4") (pin "11") (pinfunction "O_11") (pintype "output"))
    )
    (net (code "16") (name "IN_R") (class "Default")
      (node (ref "IC4") (pin "3") (pinfunction "O_3") (pintype "output"))
      (node (ref "IC7") (pin "1") (pinfunction "IN_1") (pintype "input"))
    )
    (net (code "17") (name "IN_R_INVD") (class "Default")
      (node (ref "IC4") (pin "10") (pinfunction "O_10") (pintype "output"))
      (node (ref "IC8") (pin "1") (pinfunction "IN_1") (pintype "input"))
    )
    (net (code "18") (name "MOTOR_L_+") (class "Default")
      (node (ref "C2") (pin "-") (pinfunction "-_-") (pintype "passive"))
      (node (ref "D3") (pin "A") (pinfunction "A_A") (pintype "passive"))
      (node (ref "IC2") (pin "6") (pinfunction "VS_6") (pintype "power_in"))
      (node (ref "Q1") (pin "S") (pinfunction "S_S") (pintype "passive"))
      (node (ref "Q3") (pin "D") (pinfunction "D_D") (pintype "passive"))
      (node (ref "R8") (pin "1") (pinfunction "1_1") (pintype "passive"))
      (node (ref "U$1") (pin "5A") (pinfunction "MOTOR_L_+_5A") (pintype "power_in"))
      (node (ref "U$1") (pin "5B") (pinfunction "MOTOR_L_+_5B") (pintype "power_in"))
    )
    (net (code "19") (name "MOTOR_L_-") (class "Default")
      (node (ref "C3") (pin "-") (pinfunction "-_-") (pintype "passive"))
      (node (ref "D6") (pin "A") (pinfunction "A_A") (pintype "passive"))
      (node (ref "IC3") (pin "6") (pinfunction "VS_6") (pintype "power_in"))
      (node (ref "Q2") (pin "S") (pinfunction "S_S") (pintype "passive"))
      (node (ref "Q4") (pin "D") (pinfunction "D_D") (pintype "passive"))
      (node (ref "R5") (pin "1") (pinfunction "1_1") (pintype "passive"))
      (node (ref "U$1") (pin "6A") (pinfunction "MOTOR_L_-_6A") (pintype "power_in"))
      (node (ref "U$1") (pin "6B") (pinfunction "MOTOR_L_-_6B") (pintype "power_in"))
    )
    (net (code "20") (name "MOTOR_PWM_L") (class "Default")
      (node (ref "IC4") (pin "13") (pinfunction "I1_13") (pintype "input"))
      (node (ref "IC4") (pin "6") (pinfunction "I1_6") (pintype "input"))
      (node (ref "X1") (pin "2") (pinfunction "S_2") (pintype "passive"))
    )
    (net (code "21") (name "MOTOR_PWM_R") (class "Default")
      (node (ref "IC4") (pin "2") (pinfunction "I1_2") (pintype "input"))
      (node (ref "IC4") (pin "9") (pinfunction "I1_9") (pintype "input"))
      (node (ref "X1") (pin "4") (pinfunction "S_4") (pintype "passive"))
    )
    (net (code "22") (name "MOTOR_R_+") (class "Default")
      (node (ref "C12") (pin "-") (pinfunction "-_-") (pintype "passive"))
      (node (ref "D15") (pin "A") (pinfunction "A_A") (pintype "passive"))
      (node (ref "IC7") (pin "6") (pinfunction "VS_6") (pintype "power_in"))
      (node (ref "Q10") (pin "D") (pinfunction "D_D") (pintype "passive"))
      (node (ref "Q9") (pin "S") (pinfunction "S_S") (pintype "passive"))
      (node (ref "R24") (pin "1") (pinfunction "1_1") (pintype "passive"))
      (node (ref "U$1") (pin "2A") (pinfunction "MOTOR_R_+_2A") (pintype "power_in"))
      (node (ref "U$1") (pin "2B") (pinfunction "MOTOR_R_+_2B") (pintype "power_in"))
    )
    (net (code "23") (name "MOTOR_R_-") (class "Default")
      (node (ref "C13") (pin "-") (pinfunction "-_-") (pintype "passive"))
      (node (ref "D18") (pin "A") (pinfunction "A_A") (pintype "passive"))
      (node (ref "IC8") (pin "6") (pinfunction "VS_6") (pintype "power_in"))
      (node (ref "Q11") (pin "S") (pinfunction "S_S") (pintype "passive"))
      (node (ref "Q12") (pin "D") (pinfunction "D_D") (pintype "passive"))
      (node (ref "R21") (pin "1") (pinfunction "1_1") (pintype "passive"))
      (node (ref "U$1") (pin "1A") (pinfunction "MOTOR_R_-_1A") (pintype "power_in"))
      (node (ref "U$1") (pin "1B") (pinfunction "MOTOR_R_-_1B") (pintype "power_in"))
    )
    (net (code "24") (name "Net-(D3-PadC)") (class "Default")
      (node (ref "D3") (pin "C") (pinfunction "C_C") (pintype "passive"))
      (node (ref "Q1") (pin "G") (pinfunction "G_G") (pintype "passive"))
      (node (ref "R1") (pin "2") (pinfunction "2_2") (pintype "passive"))
      (node (ref "R8") (pin "2") (pinfunction "2_2") (pintype "passive"))
    )
    (net (code "25") (name "Net-(D4-PadC)") (class "Default")
      (node (ref "D4") (pin "C") (pinfunction "C_C") (pintype "passive"))
      (node (ref "Q3") (pin "G") (pinfunction "G_G") (pintype "passive"))
      (node (ref "R2") (pin "2") (pinfunction "2_2") (pintype "passive"))
      (node (ref "R7") (pin "2") (pinfunction "2_2") (pintype "passive"))
    )
    (net (code "26") (name "Net-(D5-PadC)") (class "Default")
      (node (ref "D5") (pin "C") (pinfunction "C_C") (pintype "passive"))
      (node (ref "Q4") (pin "G") (pinfunction "G_G") (pintype "passive"))
      (node (ref "R3") (pin "1") (pinfunction "1_1") (pintype "passive"))
      (node (ref "R6") (pin "2") (pinfunction "2_2") (pintype "passive"))
    )
    (net (code "27") (name "Net-(D6-PadC)") (class "Default")
      (node (ref "D6") (pin "C") (pinfunction "C_C") (pintype "passive"))
      (node (ref "Q2") (pin "G") (pinfunction "G_G") (pintype "passive"))
      (node (ref "R4") (pin "1") (pinfunction "1_1") (pintype "passive"))
      (node (ref "R5") (pin "2") (pinfunction "2_2") (pintype "passive"))
    )
    (net (code "28") (name "Net-(D15-PadC)") (class "Default")
      (node (ref "D15") (pin "C") (pinfunction "C_C") (pintype "passive"))
      (node (ref "Q9") (pin "G") (pinfunction "G_G") (pintype "passive"))
      (node (ref "R17") (pin "2") (pinfunction "2_2") (pintype "passive"))
      (node (ref "R24") (pin "2") (pinfunction "2_2") (pintype "passive"))
    )
    (net (code "29") (name "Net-(D16-PadC)") (class "Default")
      (node (ref "D16") (pin "C") (pinfunction "C_C") (pintype "passive"))
      (node (ref "Q10") (pin "G") (pinfunction "G_G") (pintype "passive"))
      (node (ref "R18") (pin "2") (pinfunction "2_2") (pintype "passive"))
      (node (ref "R23") (pin "2") (pinfunction "2_2") (pintype "passive"))
    )
    (net (code "30") (name "Net-(D17-PadC)") (class "Default")
      (node (ref "D17") (pin "C") (pinfunction "C_C") (pintype "passive"))
      (node (ref "Q12") (pin "G") (pinfunction "G_G") (pintype "passive"))
      (node (ref "R19") (pin "1") (pinfunction "1_1") (pintype "passive"))
      (node (ref "R22") (pin "2") (pinfunction "2_2") (pintype "passive"))
    )
    (net (code "31") (name "Net-(D18-PadC)") (class "Default")
      (node (ref "D18") (pin "C") (pinfunction "C_C") (pintype "passive"))
      (node (ref "Q11") (pin "G") (pinfunction "G_G") (pintype "passive"))
      (node (ref "R20") (pin "1") (pinfunction "1_1") (pintype "passive"))
      (node (ref "R21") (pin "2") (pinfunction "2_2") (pintype "passive"))
    )
    (net (code "32") (name "Net-(IC2-HO)") (class "Default")
      (node (ref "IC2") (pin "7") (pinfunction "HO_7") (pintype "output"))
      (node (ref "R1") (pin "1") (pinfunction "1_1") (pintype "passive"))
    )
    (net (code "33") (name "Net-(IC2-LO)") (class "Default")
      (node (ref "IC2") (pin "4") (pinfunction "LO_4") (pintype "output"))
      (node (ref "R2") (pin "1") (pinfunction "1_1") (pintype "passive"))
    )
    (net (code "34") (name "Net-(IC3-HO)") (class "Default")
      (node (ref "IC3") (pin "7") (pinfunction "HO_7") (pintype "output"))
      (node (ref "R4") (pin "2") (pinfunction "2_2") (pintype "passive"))
    )
    (net (code "35") (name "Net-(IC3-LO)") (class "Default")
      (node (ref "IC3") (pin "4") (pinfunction "LO_4") (pintype "output"))
      (node (ref "R3") (pin "2") (pinfunction "2_2") (pintype "passive"))
    )
    (net (code "36") (name "Net-(IC7-HO)") (class "Default")
      (node (ref "IC7") (pin "7") (pinfunction "HO_7") (pintype "output"))
      (node (ref "R17") (pin "1") (pinfunction "1_1") (pintype "passive"))
    )
    (net (code "37") (name "Net-(IC7-LO)") (class "Default")
      (node (ref "IC7") (pin "4") (pinfunction "LO_4") (pintype "output"))
      (node (ref "R18") (pin "1") (pinfunction "1_1") (pintype "passive"))
    )
    (net (code "38") (name "Net-(IC8-HO)") (class "Default")
      (node (ref "IC8") (pin "7") (pinfunction "HO_7") (pintype "output"))
      (node (ref "R20") (pin "2") (pinfunction "2_2") (pintype "passive"))
    )
    (net (code "39") (name "Net-(IC8-LO)") (class "Default")
      (node (ref "IC8") (pin "4") (pinfunction "LO_4") (pintype "output"))
      (node (ref "R19") (pin "2") (pinfunction "2_2") (pintype "passive"))
    )
    (net (code "40") (name "Net-(IC10-+V_OUT)") (class "Default")
      (node (ref "D8") (pin "C") (pinfunction "C_C") (pintype "passive"))
      (node (ref "IC10") (pin "P$2") (pinfunction "+V_OUT_P$2") (pintype "output"))
      (node (ref "L2") (pin "1") (pinfunction "1_1") (pintype "passive"))
    )
    (net (code "41") (name "Net-(IC11-+V_OUT)") (class "Default")
      (node (ref "D7") (pin "C") (pinfunction "C_C") (pintype "passive"))
      (node (ref "IC11") (pin "P$2") (pinfunction "+V_OUT_P$2") (pintype "output"))
      (node (ref "L1") (pin "1") (pinfunction "1_1") (pintype "passive"))
    )
    (net (code "42") (name "Net-(LED1-PadA)") (class "Default")
      (node (ref "LED1") (pin "A") (pinfunction "A_A") (pintype "passive"))
      (node (ref "R14") (pin "1") (pinfunction "1_1") (pintype "passive"))
    )
    (net (code "43") (name "Net-(LED2-PadA)") (class "Default")
      (node (ref "LED2") (pin "A") (pinfunction "A_A") (pintype "passive"))
      (node (ref "R15") (pin "2") (pinfunction "2_2") (pintype "passive"))
    )
    (net (code "44") (name "RESET") (class "Default")
      (node (ref "C16") (pin "1") (pinfunction "1_1") (pintype "passive"))
      (node (ref "IC9") (pin "1") (pinfunction "PB5/PCINT5/~{RESET}/ADC0/DW_1") (pintype "bidirectional"))
      (node (ref "R9") (pin "2") (pinfunction "2_2") (pintype "passive"))
    )
    (net (code "45") (name "VB1") (class "Default")
      (node (ref "C2") (pin "+") (pinfunction "+_+") (pintype "passive"))
      (node (ref "D1") (pin "C") (pinfunction "C_C") (pintype "passive"))
      (node (ref "IC2") (pin "8") (pinfunction "VB_8") (pintype "power_in"))
    )
    (net (code "46") (name "VB2") (class "Default")
      (node (ref "C3") (pin "+") (pinfunction "+_+") (pintype "passive"))
      (node (ref "D2") (pin "C") (pinfunction "C_C") (pintype "passive"))
      (node (ref "IC3") (pin "8") (pinfunction "VB_8") (pintype "power_in"))
    )
    (net (code "47") (name "VB3") (class "Default")
      (node (ref "C12") (pin "+") (pinfunction "+_+") (pintype "passive"))
      (node (ref "D13") (pin "C") (pinfunction "C_C") (pintype "passive"))
      (node (ref "IC7") (pin "8") (pinfunction "VB_8") (pintype "power_in"))
    )
    (net (code "48") (name "VB4") (class "Default")
      (node (ref "C13") (pin "+") (pinfunction "+_+") (pintype "passive"))
      (node (ref "D14") (pin "C") (pinfunction "C_C") (pintype "passive"))
      (node (ref "IC8") (pin "8") (pinfunction "VB_8") (pintype "power_in"))
    )
    (net (code "49") (name "unconnected-(IC5C-I-Pad5)") (class "Default")
      (node (ref "IC5") (pin "5") (pinfunction "I_5") (pintype "input"))
    )
    (net (code "50") (name "unconnected-(IC5C-O-Pad6)") (class "Default")
      (node (ref "IC5") (pin "6") (pinfunction "O_6") (pintype "output"))
    )
    (net (code "51") (name "unconnected-(IC5D-I-Pad9)") (class "Default")
      (node (ref "IC5") (pin "9") (pinfunction "I_9") (pintype "input"))
    )
    (net (code "52") (name "unconnected-(IC5D-O-Pad8)") (class "Default")
      (node (ref "IC5") (pin "8") (pinfunction "O_8") (pintype "output"))
    )
    (net (code "53") (name "unconnected-(IC5E-I-Pad11)") (class "Default")
      (node (ref "IC5") (pin "11") (pinfunction "I_11") (pintype "input"))
    )
    (net (code "54") (name "unconnected-(IC5E-O-Pad10)") (class "Default")
      (node (ref "IC5") (pin "10") (pinfunction "O_10") (pintype "output"))
    )
    (net (code "55") (name "unconnected-(IC5F-I-Pad13)") (class "Default")
      (node (ref "IC5") (pin "13") (pinfunction "I_13") (pintype "input"))
    )
    (net (code "56") (name "unconnected-(IC5F-O-Pad12)") (class "Default")
      (node (ref "IC5") (pin "12") (pinfunction "O_12") (pintype "output"))
    )
    (net (code "57") (name "unconnected-(IC9-PB1{slash}PCINT1{slash}AIN1{slash}OC0B{slash}INT0{slash}MISO-Pad6)") (class "Default")
      (node (ref "IC9") (pin "6") (pinfunction "PB1/PCINT1/AIN1/OC0B/INT0/MISO_6") (pintype "bidirectional"))
    )
    (net (code "58") (name "unconnected-(IC9-PB2{slash}PCINT2{slash}SCK{slash}ADC1{slash}T0-Pad7)") (class "Default")
      (node (ref "IC9") (pin "7") (pinfunction "PB2/PCINT2/SCK/ADC1/T0_7") (pintype "bidirectional"))
    )
    (net (code "59") (name "unconnected-(IC9-PB3{slash}PCINT3{slash}CLKI{slash}ADC3-Pad2)") (class "Default")
      (node (ref "IC9") (pin "2") (pinfunction "PB3/PCINT3/CLKI/ADC3_2") (pintype "bidirectional"))
    )
    (net (code "60") (name "unconnected-(R10-Pad1)") (class "Default")
      (node (ref "R10") (pin "1") (pinfunction "1_1") (pintype "passive"))
    )
  )
)
